# Tracksoar_Breakout_Shield.net
KiCad netlist of a schematic drawn in EAGLE
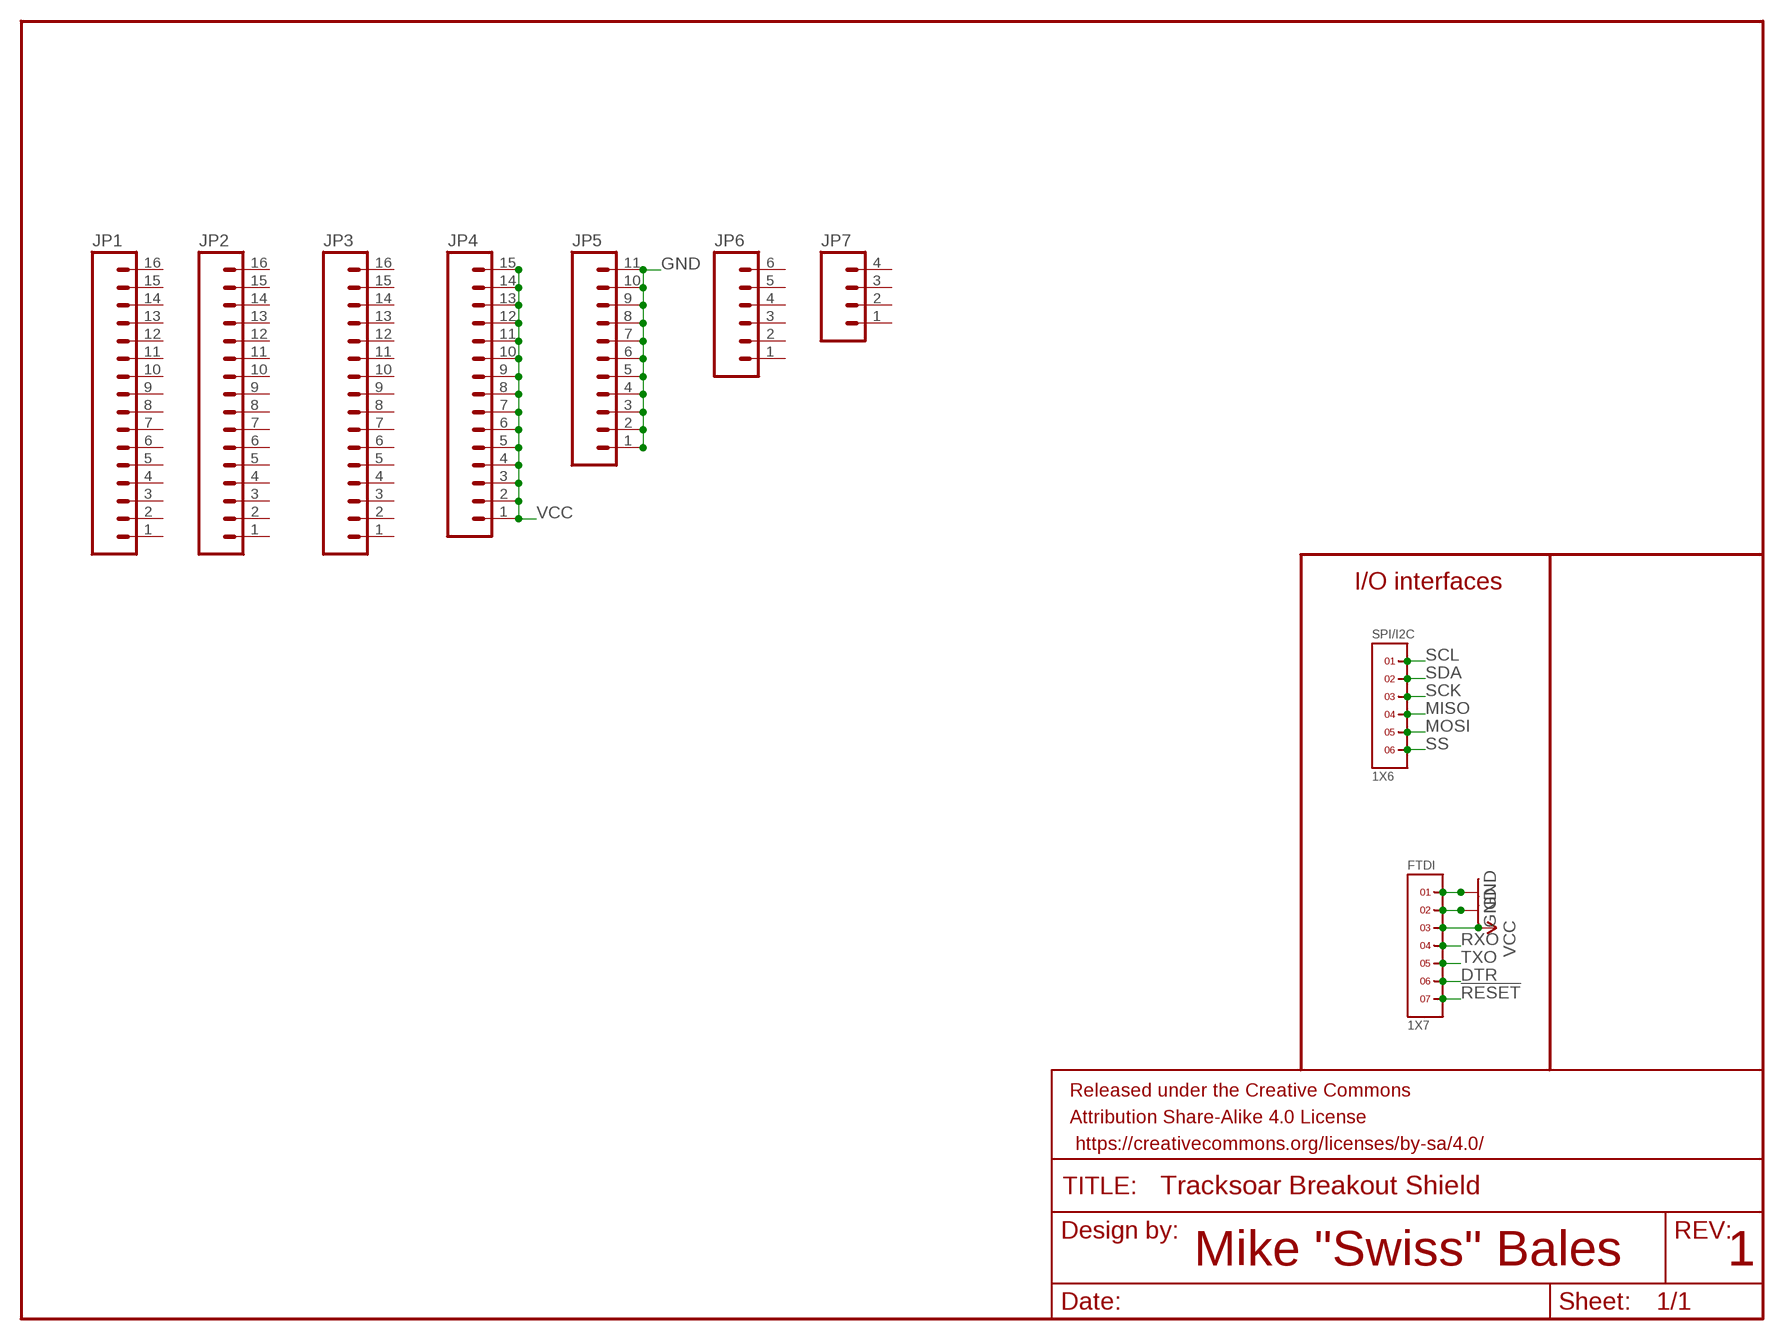
[diagram p0: schematic, sheet 1]

(export (version "E")
  (design (tool "Eeschema 10.0.6"))
  (components
    (comp (ref "FRAME1")
      (value "FRAME-LETTER")
      (footprint "eagle-import:CREATIVE_COMMONS")
      (libsource (lib "eagle-import") (part "FRAME-LETTER"))
    )
    (comp (ref "FTDI")
      (value "1X7")
      (footprint "eagle-import:1X7")
      (libsource (lib "eagle-import") (part "1X7"))
    )
    (comp (ref "JP1")
      (value "M161X16_NO_SILK")
      (footprint "eagle-import:1X16_NO_SILK")
      (libsource (lib "eagle-import") (part "M161X16_NO_SILK"))
    )
    (comp (ref "JP2")
      (value "M161X16_NO_SILK")
      (footprint "eagle-import:1X16_NO_SILK")
      (libsource (lib "eagle-import") (part "M161X16_NO_SILK"))
    )
    (comp (ref "JP3")
      (value "M161X16_NO_SILK")
      (footprint "eagle-import:1X16_NO_SILK")
      (libsource (lib "eagle-import") (part "M161X16_NO_SILK"))
    )
    (comp (ref "JP4")
      (value "M15")
      (footprint "eagle-import:1X15")
      (libsource (lib "eagle-import") (part "M15"))
    )
    (comp (ref "JP5")
      (value "M11PTH")
      (footprint "eagle-import:1X11")
      (libsource (lib "eagle-import") (part "M11PTH"))
    )
    (comp (ref "JP6")
      (value "M06NO_SILK_FEMALE_PTH")
      (footprint "eagle-import:1X06_NO_SILK")
      (libsource (lib "eagle-import") (part "M06NO_SILK_FEMALE_PTH"))
    )
    (comp (ref "JP7")
      (value "M04NO_SILK_ALL_ROUND")
      (footprint "eagle-import:1X04_NO_SILK_ALL_ROUND")
      (libsource (lib "eagle-import") (part "M04NO_SILK_ALL_ROUND"))
    )
    (comp (ref "SPI/I2C")
      (value "1X6")
      (footprint "eagle-import:1X6")
      (libsource (lib "eagle-import") (part "1X6"))
    )
  )
  (nets
    (net (code "1") (name "/DTR") (class "Default")
      (node (ref "FTDI") (pin "6") (pinfunction "6_6") (pintype "bidirectional"))
    )
    (net (code "2") (name "/MISO") (class "Default")
      (node (ref "SPI/I2C") (pin "4") (pinfunction "4_4") (pintype "bidirectional"))
    )
    (net (code "3") (name "/MOSI") (class "Default")
      (node (ref "SPI/I2C") (pin "5") (pinfunction "5_5") (pintype "bidirectional"))
    )
    (net (code "4") (name "/RXO") (class "Default")
      (node (ref "FTDI") (pin "4") (pinfunction "4_4") (pintype "bidirectional"))
    )
    (net (code "5") (name "/SCK") (class "Default")
      (node (ref "SPI/I2C") (pin "3") (pinfunction "3_3") (pintype "bidirectional"))
    )
    (net (code "6") (name "/SCL") (class "Default")
      (node (ref "SPI/I2C") (pin "1") (pinfunction "1_1") (pintype "bidirectional"))
    )
    (net (code "7") (name "/SDA") (class "Default")
      (node (ref "SPI/I2C") (pin "2") (pinfunction "2_2") (pintype "bidirectional"))
    )
    (net (code "8") (name "/SS") (class "Default")
      (node (ref "SPI/I2C") (pin "6") (pinfunction "6_6") (pintype "bidirectional"))
    )
    (net (code "9") (name "/TXO") (class "Default")
      (node (ref "FTDI") (pin "5") (pinfunction "5_5") (pintype "bidirectional"))
    )
    (net (code "10") (name "/~{RESET}") (class "Default")
      (node (ref "FTDI") (pin "7") (pinfunction "7_7") (pintype "bidirectional"))
    )
    (net (code "11") (name "GND") (class "Default")
      (node (ref "FTDI") (pin "1") (pinfunction "1_1") (pintype "bidirectional"))
      (node (ref "FTDI") (pin "2") (pinfunction "2_2") (pintype "bidirectional"))
      (node (ref "JP5") (pin "1") (pinfunction "1_1") (pintype "passive"))
      (node (ref "JP5") (pin "10") (pinfunction "10_10") (pintype "passive"))
      (node (ref "JP5") (pin "11") (pinfunction "11_11") (pintype "passive"))
      (node (ref "JP5") (pin "2") (pinfunction "2_2") (pintype "passive"))
      (node (ref "JP5") (pin "3") (pinfunction "3_3") (pintype "passive"))
      (node (ref "JP5") (pin "4") (pinfunction "4_4") (pintype "passive"))
      (node (ref "JP5") (pin "5") (pinfunction "5_5") (pintype "passive"))
      (node (ref "JP5") (pin "6") (pinfunction "6_6") (pintype "passive"))
      (node (ref "JP5") (pin "7") (pinfunction "7_7") (pintype "passive"))
      (node (ref "JP5") (pin "8") (pinfunction "8_8") (pintype "passive"))
      (node (ref "JP5") (pin "9") (pinfunction "9_9") (pintype "passive"))
    )
    (net (code "12") (name "VCC") (class "Default")
      (node (ref "FTDI") (pin "3") (pinfunction "3_3") (pintype "bidirectional"))
      (node (ref "JP4") (pin "1") (pinfunction "1_1") (pintype "passive"))
      (node (ref "JP4") (pin "10") (pinfunction "10_10") (pintype "passive"))
      (node (ref "JP4") (pin "11") (pinfunction "11_11") (pintype "passive"))
      (node (ref "JP4") (pin "12") (pinfunction "12_12") (pintype "passive"))
      (node (ref "JP4") (pin "13") (pinfunction "13_13") (pintype "passive"))
      (node (ref "JP4") (pin "14") (pinfunction "14_14") (pintype "passive"))
      (node (ref "JP4") (pin "15") (pinfunction "15_15") (pintype "passive"))
      (node (ref "JP4") (pin "2") (pinfunction "2_2") (pintype "passive"))
      (node (ref "JP4") (pin "3") (pinfunction "3_3") (pintype "passive"))
      (node (ref "JP4") (pin "4") (pinfunction "4_4") (pintype "passive"))
      (node (ref "JP4") (pin "5") (pinfunction "5_5") (pintype "passive"))
      (node (ref "JP4") (pin "6") (pinfunction "6_6") (pintype "passive"))
      (node (ref "JP4") (pin "7") (pinfunction "7_7") (pintype "passive"))
      (node (ref "JP4") (pin "8") (pinfunction "8_8") (pintype "passive"))
      (node (ref "JP4") (pin "9") (pinfunction "9_9") (pintype "passive"))
    )
    (net (code "13") (name "unconnected-(JP1-Pad1)") (class "Default")
      (node (ref "JP1") (pin "1") (pinfunction "1_1") (pintype "passive"))
    )
    (net (code "14") (name "unconnected-(JP1-Pad2)") (class "Default")
      (node (ref "JP1") (pin "2") (pinfunction "2_2") (pintype "passive"))
    )
    (net (code "15") (name "unconnected-(JP1-Pad3)") (class "Default")
      (node (ref "JP1") (pin "3") (pinfunction "3_3") (pintype "passive"))
    )
    (net (code "16") (name "unconnected-(JP1-Pad4)") (class "Default")
      (node (ref "JP1") (pin "4") (pinfunction "4_4") (pintype "passive"))
    )
    (net (code "17") (name "unconnected-(JP1-Pad5)") (class "Default")
      (node (ref "JP1") (pin "5") (pinfunction "5_5") (pintype "passive"))
    )
    (net (code "18") (name "unconnected-(JP1-Pad6)") (class "Default")
      (node (ref "JP1") (pin "6") (pinfunction "6_6") (pintype "passive"))
    )
    (net (code "19") (name "unconnected-(JP1-Pad7)") (class "Default")
      (node (ref "JP1") (pin "7") (pinfunction "7_7") (pintype "passive"))
    )
    (net (code "20") (name "unconnected-(JP1-Pad8)") (class "Default")
      (node (ref "JP1") (pin "8") (pinfunction "8_8") (pintype "passive"))
    )
    (net (code "21") (name "unconnected-(JP1-Pad9)") (class "Default")
      (node (ref "JP1") (pin "9") (pinfunction "9_9") (pintype "passive"))
    )
    (net (code "22") (name "unconnected-(JP1-Pad10)") (class "Default")
      (node (ref "JP1") (pin "10") (pinfunction "10_10") (pintype "passive"))
    )
    (net (code "23") (name "unconnected-(JP1-Pad11)") (class "Default")
      (node (ref "JP1") (pin "11") (pinfunction "11_11") (pintype "passive"))
    )
    (net (code "24") (name "unconnected-(JP1-Pad12)") (class "Default")
      (node (ref "JP1") (pin "12") (pinfunction "12_12") (pintype "passive"))
    )
    (net (code "25") (name "unconnected-(JP1-Pad13)") (class "Default")
      (node (ref "JP1") (pin "13") (pinfunction "13_13") (pintype "passive"))
    )
    (net (code "26") (name "unconnected-(JP1-Pad14)") (class "Default")
      (node (ref "JP1") (pin "14") (pinfunction "14_14") (pintype "passive"))
    )
    (net (code "27") (name "unconnected-(JP1-Pad15)") (class "Default")
      (node (ref "JP1") (pin "15") (pinfunction "15_15") (pintype "passive"))
    )
    (net (code "28") (name "unconnected-(JP1-Pad16)") (class "Default")
      (node (ref "JP1") (pin "16") (pinfunction "16_16") (pintype "passive"))
    )
    (net (code "29") (name "unconnected-(JP2-Pad1)") (class "Default")
      (node (ref "JP2") (pin "1") (pinfunction "1_1") (pintype "passive"))
    )
    (net (code "30") (name "unconnected-(JP2-Pad2)") (class "Default")
      (node (ref "JP2") (pin "2") (pinfunction "2_2") (pintype "passive"))
    )
    (net (code "31") (name "unconnected-(JP2-Pad3)") (class "Default")
      (node (ref "JP2") (pin "3") (pinfunction "3_3") (pintype "passive"))
    )
    (net (code "32") (name "unconnected-(JP2-Pad4)") (class "Default")
      (node (ref "JP2") (pin "4") (pinfunction "4_4") (pintype "passive"))
    )
    (net (code "33") (name "unconnected-(JP2-Pad5)") (class "Default")
      (node (ref "JP2") (pin "5") (pinfunction "5_5") (pintype "passive"))
    )
    (net (code "34") (name "unconnected-(JP2-Pad6)") (class "Default")
      (node (ref "JP2") (pin "6") (pinfunction "6_6") (pintype "passive"))
    )
    (net (code "35") (name "unconnected-(JP2-Pad7)") (class "Default")
      (node (ref "JP2") (pin "7") (pinfunction "7_7") (pintype "passive"))
    )
    (net (code "36") (name "unconnected-(JP2-Pad8)") (class "Default")
      (node (ref "JP2") (pin "8") (pinfunction "8_8") (pintype "passive"))
    )
    (net (code "37") (name "unconnected-(JP2-Pad9)") (class "Default")
      (node (ref "JP2") (pin "9") (pinfunction "9_9") (pintype "passive"))
    )
    (net (code "38") (name "unconnected-(JP2-Pad10)") (class "Default")
      (node (ref "JP2") (pin "10") (pinfunction "10_10") (pintype "passive"))
    )
    (net (code "39") (name "unconnected-(JP2-Pad11)") (class "Default")
      (node (ref "JP2") (pin "11") (pinfunction "11_11") (pintype "passive"))
    )
    (net (code "40") (name "unconnected-(JP2-Pad12)") (class "Default")
      (node (ref "JP2") (pin "12") (pinfunction "12_12") (pintype "passive"))
    )
    (net (code "41") (name "unconnected-(JP2-Pad13)") (class "Default")
      (node (ref "JP2") (pin "13") (pinfunction "13_13") (pintype "passive"))
    )
    (net (code "42") (name "unconnected-(JP2-Pad14)") (class "Default")
      (node (ref "JP2") (pin "14") (pinfunction "14_14") (pintype "passive"))
    )
    (net (code "43") (name "unconnected-(JP2-Pad15)") (class "Default")
      (node (ref "JP2") (pin "15") (pinfunction "15_15") (pintype "passive"))
    )
    (net (code "44") (name "unconnected-(JP2-Pad16)") (class "Default")
      (node (ref "JP2") (pin "16") (pinfunction "16_16") (pintype "passive"))
    )
    (net (code "45") (name "unconnected-(JP3-Pad1)") (class "Default")
      (node (ref "JP3") (pin "1") (pinfunction "1_1") (pintype "passive"))
    )
    (net (code "46") (name "unconnected-(JP3-Pad2)") (class "Default")
      (node (ref "JP3") (pin "2") (pinfunction "2_2") (pintype "passive"))
    )
    (net (code "47") (name "unconnected-(JP3-Pad3)") (class "Default")
      (node (ref "JP3") (pin "3") (pinfunction "3_3") (pintype "passive"))
    )
    (net (code "48") (name "unconnected-(JP3-Pad4)") (class "Default")
      (node (ref "JP3") (pin "4") (pinfunction "4_4") (pintype "passive"))
    )
    (net (code "49") (name "unconnected-(JP3-Pad5)") (class "Default")
      (node (ref "JP3") (pin "5") (pinfunction "5_5") (pintype "passive"))
    )
    (net (code "50") (name "unconnected-(JP3-Pad6)") (class "Default")
      (node (ref "JP3") (pin "6") (pinfunction "6_6") (pintype "passive"))
    )
    (net (code "51") (name "unconnected-(JP3-Pad7)") (class "Default")
      (node (ref "JP3") (pin "7") (pinfunction "7_7") (pintype "passive"))
    )
    (net (code "52") (name "unconnected-(JP3-Pad8)") (class "Default")
      (node (ref "JP3") (pin "8") (pinfunction "8_8") (pintype "passive"))
    )
    (net (code "53") (name "unconnected-(JP3-Pad9)") (class "Default")
      (node (ref "JP3") (pin "9") (pinfunction "9_9") (pintype "passive"))
    )
    (net (code "54") (name "unconnected-(JP3-Pad10)") (class "Default")
      (node (ref "JP3") (pin "10") (pinfunction "10_10") (pintype "passive"))
    )
    (net (code "55") (name "unconnected-(JP3-Pad11)") (class "Default")
      (node (ref "JP3") (pin "11") (pinfunction "11_11") (pintype "passive"))
    )
    (net (code "56") (name "unconnected-(JP3-Pad12)") (class "Default")
      (node (ref "JP3") (pin "12") (pinfunction "12_12") (pintype "passive"))
    )
    (net (code "57") (name "unconnected-(JP3-Pad13)") (class "Default")
      (node (ref "JP3") (pin "13") (pinfunction "13_13") (pintype "passive"))
    )
    (net (code "58") (name "unconnected-(JP3-Pad14)") (class "Default")
      (node (ref "JP3") (pin "14") (pinfunction "14_14") (pintype "passive"))
    )
    (net (code "59") (name "unconnected-(JP3-Pad15)") (class "Default")
      (node (ref "JP3") (pin "15") (pinfunction "15_15") (pintype "passive"))
    )
    (net (code "60") (name "unconnected-(JP3-Pad16)") (class "Default")
      (node (ref "JP3") (pin "16") (pinfunction "16_16") (pintype "passive"))
    )
    (net (code "61") (name "unconnected-(JP6-Pad1)") (class "Default")
      (node (ref "JP6") (pin "1") (pinfunction "1_1") (pintype "passive"))
    )
    (net (code "62") (name "unconnected-(JP6-Pad2)") (class "Default")
      (node (ref "JP6") (pin "2") (pinfunction "2_2") (pintype "passive"))
    )
    (net (code "63") (name "unconnected-(JP6-Pad3)") (class "Default")
      (node (ref "JP6") (pin "3") (pinfunction "3_3") (pintype "passive"))
    )
    (net (code "64") (name "unconnected-(JP6-Pad4)") (class "Default")
      (node (ref "JP6") (pin "4") (pinfunction "4_4") (pintype "passive"))
    )
    (net (code "65") (name "unconnected-(JP6-Pad5)") (class "Default")
      (node (ref "JP6") (pin "5") (pinfunction "5_5") (pintype "passive"))
    )
    (net (code "66") (name "unconnected-(JP6-Pad6)") (class "Default")
      (node (ref "JP6") (pin "6") (pinfunction "6_6") (pintype "passive"))
    )
    (net (code "67") (name "unconnected-(JP7-Pad1)") (class "Default")
      (node (ref "JP7") (pin "1") (pinfunction "1_1") (pintype "passive"))
    )
    (net (code "68") (name "unconnected-(JP7-Pad2)") (class "Default")
      (node (ref "JP7") (pin "2") (pinfunction "2_2") (pintype "passive"))
    )
    (net (code "69") (name "unconnected-(JP7-Pad3)") (class "Default")
      (node (ref "JP7") (pin "3") (pinfunction "3_3") (pintype "passive"))
    )
    (net (code "70") (name "unconnected-(JP7-Pad4)") (class "Default")
      (node (ref "JP7") (pin "4") (pinfunction "4_4") (pintype "passive"))
    )
  )
)
